# Pendu_LED_10mm.net
KiCad netlist of a schematic drawn in EasyEDA
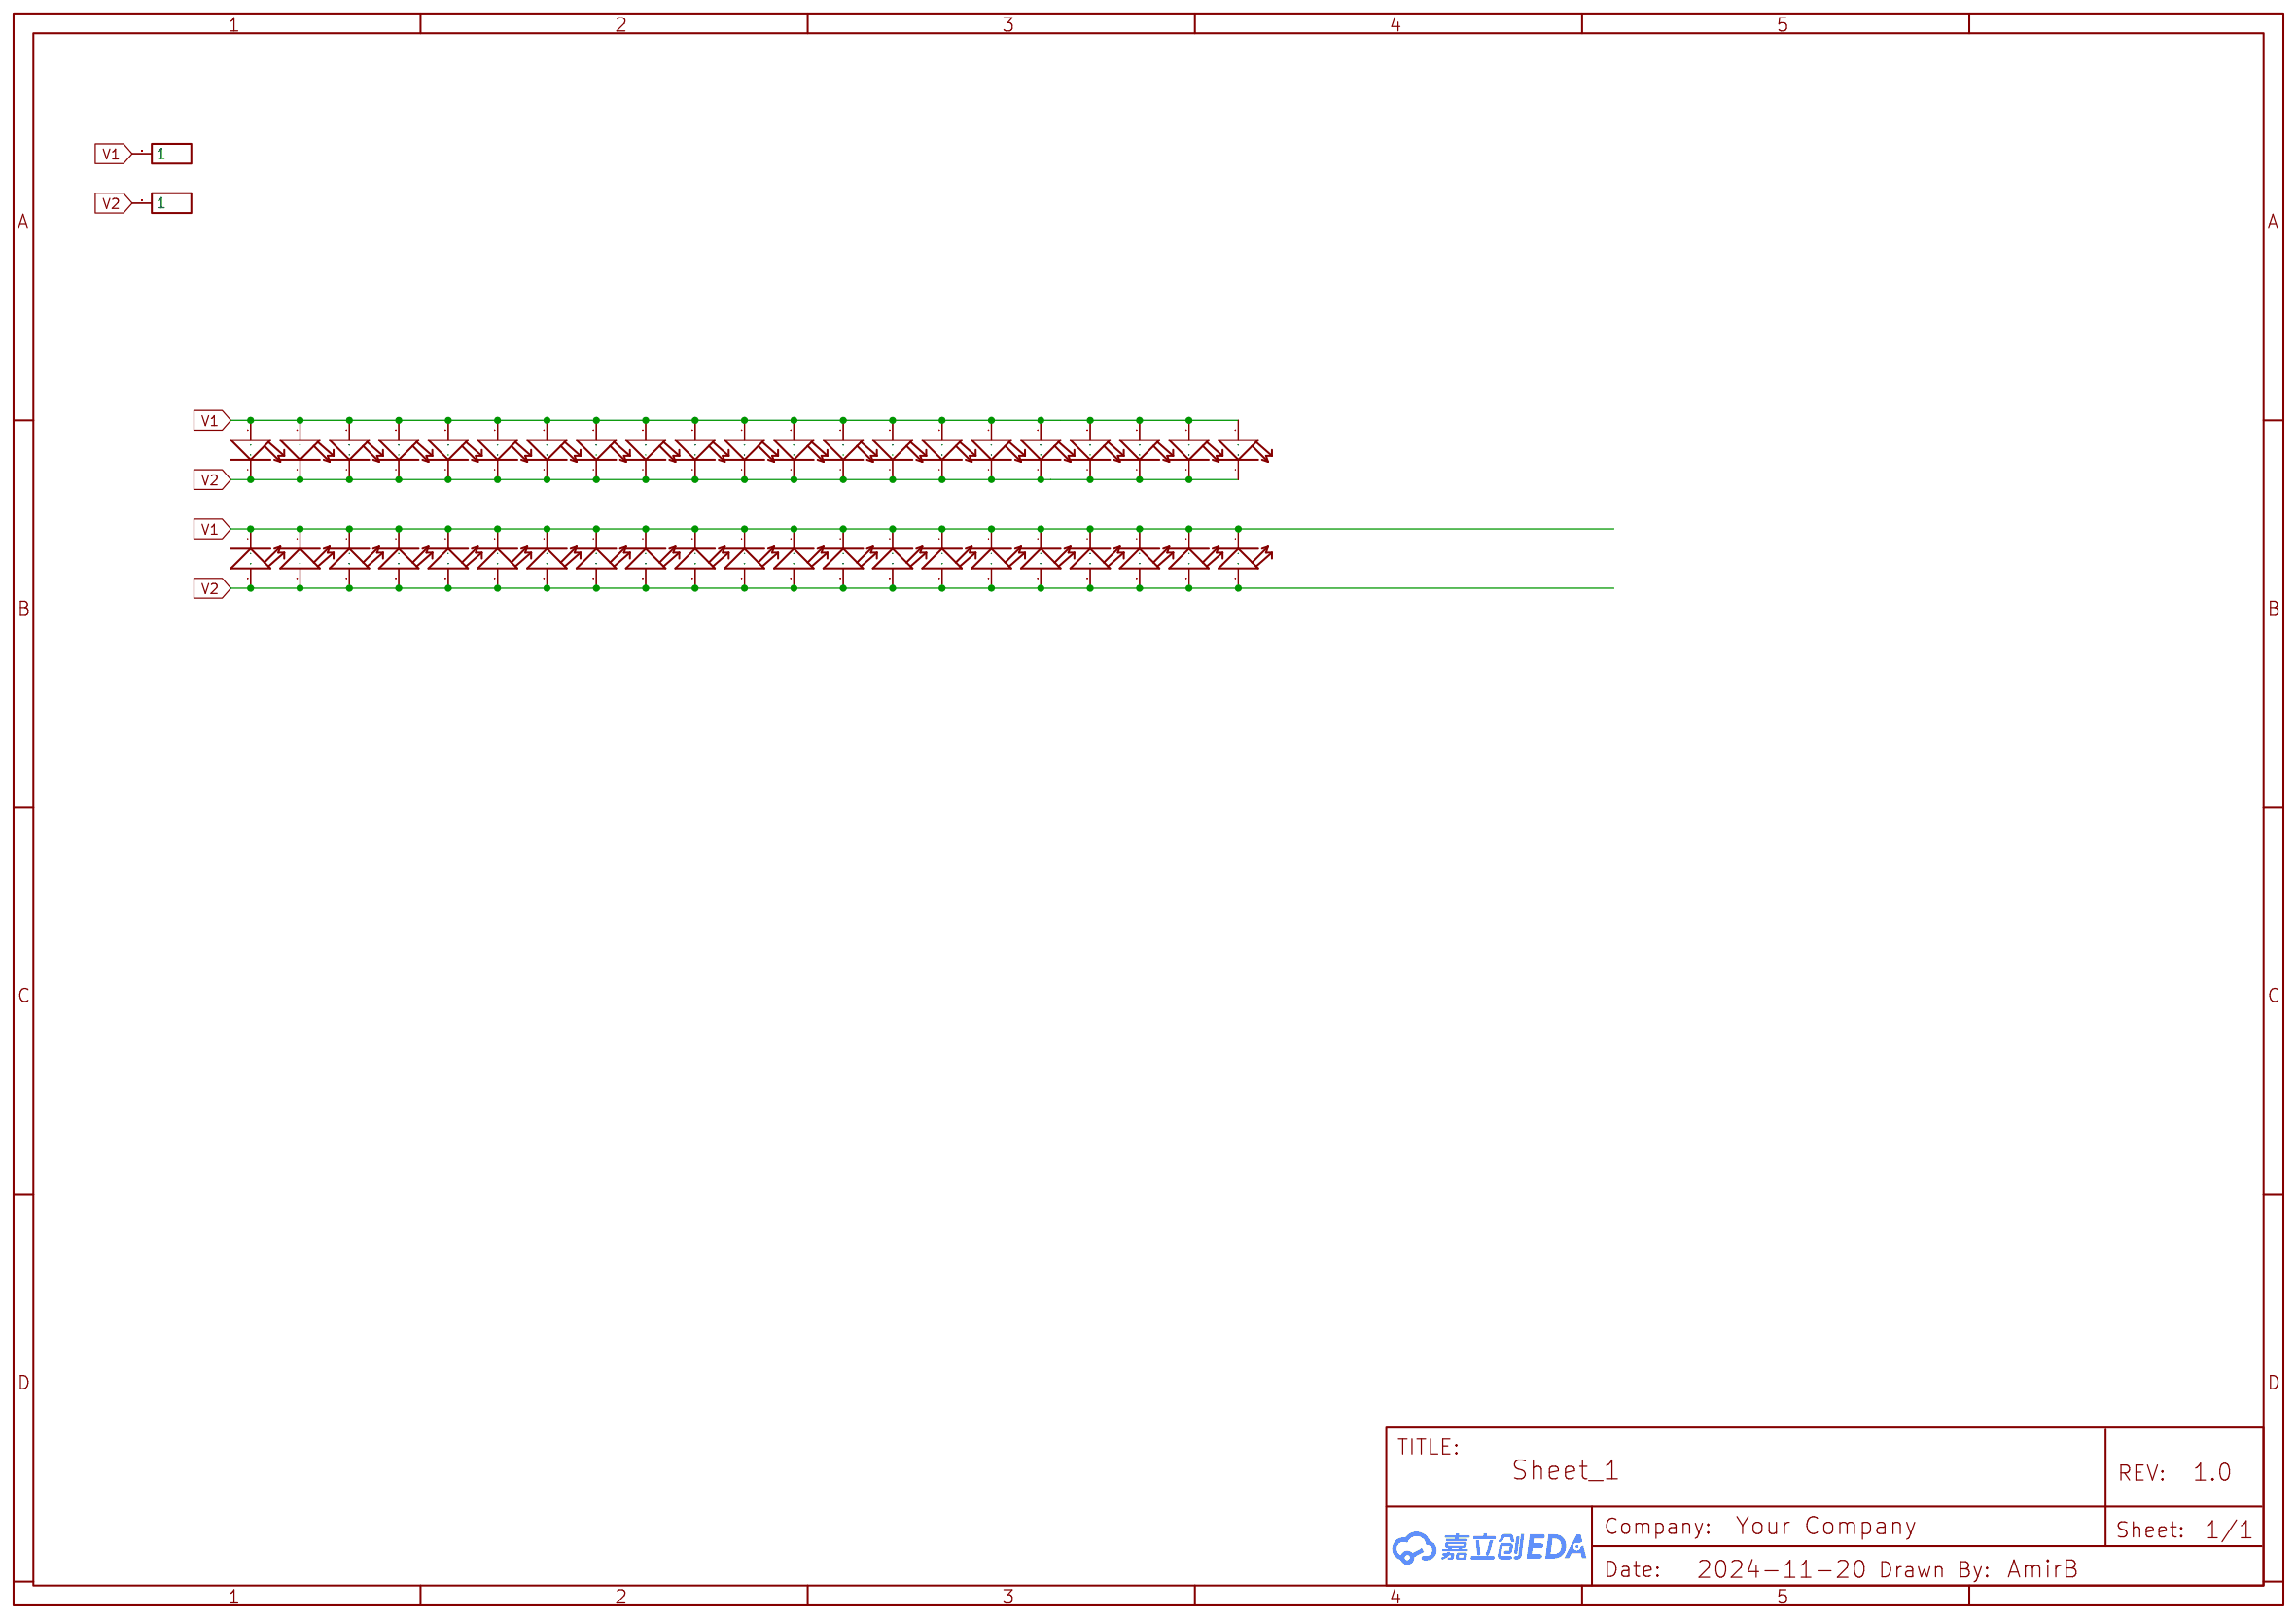
[diagram p0: schematic sheet]

(export (version "E")
  (design (tool "Eeschema 10.0.6"))
  (components
    (comp (ref "J1")
      (value "HDR-M-2.54_1x1")
      (fields (field (name "BOM_Supplier Part") "C81276"))
      (libsource (lib "") (part "HDR-M-2.54_1x1"))
    )
    (comp (ref "J2")
      (value "HDR-M-2.54_1x1")
      (fields (field (name "BOM_Supplier Part") "C81276"))
      (libsource (lib "") (part "HDR-M-2.54_1x1"))
    )
    (comp (ref "LD1") (value "1004OUW") (libsource (lib "") (part "1004OUW_1")))
    (comp (ref "LD2") (value "1004OUW") (libsource (lib "") (part "1004OUW_1")))
    (comp (ref "LD3") (value "1004OUW") (libsource (lib "") (part "1004OUW_1")))
    (comp (ref "LD4") (value "1004OUW") (libsource (lib "") (part "1004OUW_1")))
    (comp (ref "LD5") (value "1004OUW") (libsource (lib "") (part "1004OUW_1")))
    (comp (ref "LD6") (value "1004OUW") (libsource (lib "") (part "1004OUW_1")))
    (comp (ref "LD7") (value "1004OUW") (libsource (lib "") (part "1004OUW_1")))
    (comp (ref "LD8") (value "1004OUW") (libsource (lib "") (part "1004OUW_1")))
    (comp (ref "LD9") (value "1004OUW") (libsource (lib "") (part "1004OUW_1")))
    (comp (ref "LD10") (value "1004OUW") (libsource (lib "") (part "1004OUW_1")))
    (comp (ref "LD11") (value "1004OUW") (libsource (lib "") (part "1004OUW_1")))
    (comp (ref "LD12") (value "1004OUW") (libsource (lib "") (part "1004OUW_1")))
    (comp (ref "LD13") (value "1004OUW") (libsource (lib "") (part "1004OUW_1")))
    (comp (ref "LD14") (value "1004OUW") (libsource (lib "") (part "1004OUW_1")))
    (comp (ref "LD15") (value "1004OUW") (libsource (lib "") (part "1004OUW_1")))
    (comp (ref "LD16") (value "1004OUW") (libsource (lib "") (part "1004OUW_1")))
    (comp (ref "LD17") (value "1004OUW") (libsource (lib "") (part "1004OUW_1")))
    (comp (ref "LD18") (value "1004OUW") (libsource (lib "") (part "1004OUW_1")))
    (comp (ref "LD19") (value "1004OUW") (libsource (lib "") (part "1004OUW_1")))
    (comp (ref "LD20") (value "1004OUW") (libsource (lib "") (part "1004OUW_1")))
    (comp (ref "LD21") (value "1004OUW") (libsource (lib "") (part "1004OUW_1")))
    (comp (ref "LU1") (value "1004OUW") (libsource (lib "") (part "1004OUW")))
    (comp (ref "LU2") (value "1004OUW") (libsource (lib "") (part "1004OUW")))
    (comp (ref "LU3") (value "1004OUW") (libsource (lib "") (part "1004OUW")))
    (comp (ref "LU4") (value "1004OUW") (libsource (lib "") (part "1004OUW")))
    (comp (ref "LU5") (value "1004OUW") (libsource (lib "") (part "1004OUW")))
    (comp (ref "LU6") (value "1004OUW") (libsource (lib "") (part "1004OUW")))
    (comp (ref "LU7") (value "1004OUW") (libsource (lib "") (part "1004OUW")))
    (comp (ref "LU8") (value "1004OUW") (libsource (lib "") (part "1004OUW")))
    (comp (ref "LU9") (value "1004OUW") (libsource (lib "") (part "1004OUW")))
    (comp (ref "LU10") (value "1004OUW") (libsource (lib "") (part "1004OUW")))
    (comp (ref "LU11") (value "1004OUW") (libsource (lib "") (part "1004OUW")))
    (comp (ref "LU12") (value "1004OUW") (libsource (lib "") (part "1004OUW")))
    (comp (ref "LU13") (value "1004OUW") (libsource (lib "") (part "1004OUW")))
    (comp (ref "LU14") (value "1004OUW") (libsource (lib "") (part "1004OUW")))
    (comp (ref "LU15") (value "1004OUW") (libsource (lib "") (part "1004OUW")))
    (comp (ref "LU16") (value "1004OUW") (libsource (lib "") (part "1004OUW")))
    (comp (ref "LU17") (value "1004OUW") (libsource (lib "") (part "1004OUW")))
    (comp (ref "LU18") (value "1004OUW") (libsource (lib "") (part "1004OUW")))
    (comp (ref "LU19") (value "1004OUW") (libsource (lib "") (part "1004OUW")))
    (comp (ref "LU20") (value "1004OUW") (libsource (lib "") (part "1004OUW")))
    (comp (ref "LU21") (value "1004OUW") (libsource (lib "") (part "1004OUW")))
  )
  (nets
    (net (code "1") (name "V1") (class "Default")
      (node (ref "J1") (pin "1") (pinfunction "1_1") (pintype "input"))
      (node (ref "LD1") (pin "-") (pinfunction "-_-") (pintype "unspecified"))
      (node (ref "LD10") (pin "-") (pinfunction "-_-") (pintype "unspecified"))
      (node (ref "LD11") (pin "-") (pinfunction "-_-") (pintype "unspecified"))
      (node (ref "LD12") (pin "-") (pinfunction "-_-") (pintype "unspecified"))
      (node (ref "LD13") (pin "-") (pinfunction "-_-") (pintype "unspecified"))
      (node (ref "LD14") (pin "-") (pinfunction "-_-") (pintype "unspecified"))
      (node (ref "LD15") (pin "-") (pinfunction "-_-") (pintype "unspecified"))
      (node (ref "LD16") (pin "-") (pinfunction "-_-") (pintype "unspecified"))
      (node (ref "LD17") (pin "-") (pinfunction "-_-") (pintype "unspecified"))
      (node (ref "LD18") (pin "-") (pinfunction "-_-") (pintype "unspecified"))
      (node (ref "LD19") (pin "-") (pinfunction "-_-") (pintype "unspecified"))
      (node (ref "LD2") (pin "-") (pinfunction "-_-") (pintype "unspecified"))
      (node (ref "LD20") (pin "-") (pinfunction "-_-") (pintype "unspecified"))
      (node (ref "LD21") (pin "-") (pinfunction "-_-") (pintype "unspecified"))
      (node (ref "LD3") (pin "-") (pinfunction "-_-") (pintype "unspecified"))
      (node (ref "LD4") (pin "-") (pinfunction "-_-") (pintype "unspecified"))
      (node (ref "LD5") (pin "-") (pinfunction "-_-") (pintype "unspecified"))
      (node (ref "LD6") (pin "-") (pinfunction "-_-") (pintype "unspecified"))
      (node (ref "LD7") (pin "-") (pinfunction "-_-") (pintype "unspecified"))
      (node (ref "LD8") (pin "-") (pinfunction "-_-") (pintype "unspecified"))
      (node (ref "LD9") (pin "-") (pinfunction "-_-") (pintype "unspecified"))
      (node (ref "LU1") (pin "+") (pinfunction "+_+") (pintype "unspecified"))
      (node (ref "LU10") (pin "+") (pinfunction "+_+") (pintype "unspecified"))
      (node (ref "LU11") (pin "+") (pinfunction "+_+") (pintype "unspecified"))
      (node (ref "LU12") (pin "+") (pinfunction "+_+") (pintype "unspecified"))
      (node (ref "LU13") (pin "+") (pinfunction "+_+") (pintype "unspecified"))
      (node (ref "LU14") (pin "+") (pinfunction "+_+") (pintype "unspecified"))
      (node (ref "LU15") (pin "+") (pinfunction "+_+") (pintype "unspecified"))
      (node (ref "LU16") (pin "+") (pinfunction "+_+") (pintype "unspecified"))
      (node (ref "LU17") (pin "+") (pinfunction "+_+") (pintype "unspecified"))
      (node (ref "LU18") (pin "+") (pinfunction "+_+") (pintype "unspecified"))
      (node (ref "LU19") (pin "+") (pinfunction "+_+") (pintype "unspecified"))
      (node (ref "LU2") (pin "+") (pinfunction "+_+") (pintype "unspecified"))
      (node (ref "LU20") (pin "+") (pinfunction "+_+") (pintype "unspecified"))
      (node (ref "LU21") (pin "+") (pinfunction "+_+") (pintype "unspecified"))
      (node (ref "LU3") (pin "+") (pinfunction "+_+") (pintype "unspecified"))
      (node (ref "LU4") (pin "+") (pinfunction "+_+") (pintype "unspecified"))
      (node (ref "LU5") (pin "+") (pinfunction "+_+") (pintype "unspecified"))
      (node (ref "LU6") (pin "+") (pinfunction "+_+") (pintype "unspecified"))
      (node (ref "LU7") (pin "+") (pinfunction "+_+") (pintype "unspecified"))
      (node (ref "LU8") (pin "+") (pinfunction "+_+") (pintype "unspecified"))
      (node (ref "LU9") (pin "+") (pinfunction "+_+") (pintype "unspecified"))
    )
    (net (code "2") (name "V2") (class "Default")
      (node (ref "J2") (pin "1") (pinfunction "1_1") (pintype "input"))
      (node (ref "LD1") (pin "+") (pinfunction "+_+") (pintype "unspecified"))
      (node (ref "LD10") (pin "+") (pinfunction "+_+") (pintype "unspecified"))
      (node (ref "LD11") (pin "+") (pinfunction "+_+") (pintype "unspecified"))
      (node (ref "LD12") (pin "+") (pinfunction "+_+") (pintype "unspecified"))
      (node (ref "LD13") (pin "+") (pinfunction "+_+") (pintype "unspecified"))
      (node (ref "LD14") (pin "+") (pinfunction "+_+") (pintype "unspecified"))
      (node (ref "LD15") (pin "+") (pinfunction "+_+") (pintype "unspecified"))
      (node (ref "LD16") (pin "+") (pinfunction "+_+") (pintype "unspecified"))
      (node (ref "LD17") (pin "+") (pinfunction "+_+") (pintype "unspecified"))
      (node (ref "LD18") (pin "+") (pinfunction "+_+") (pintype "unspecified"))
      (node (ref "LD19") (pin "+") (pinfunction "+_+") (pintype "unspecified"))
      (node (ref "LD2") (pin "+") (pinfunction "+_+") (pintype "unspecified"))
      (node (ref "LD20") (pin "+") (pinfunction "+_+") (pintype "unspecified"))
      (node (ref "LD21") (pin "+") (pinfunction "+_+") (pintype "unspecified"))
      (node (ref "LD3") (pin "+") (pinfunction "+_+") (pintype "unspecified"))
      (node (ref "LD4") (pin "+") (pinfunction "+_+") (pintype "unspecified"))
      (node (ref "LD5") (pin "+") (pinfunction "+_+") (pintype "unspecified"))
      (node (ref "LD6") (pin "+") (pinfunction "+_+") (pintype "unspecified"))
      (node (ref "LD7") (pin "+") (pinfunction "+_+") (pintype "unspecified"))
      (node (ref "LD8") (pin "+") (pinfunction "+_+") (pintype "unspecified"))
      (node (ref "LD9") (pin "+") (pinfunction "+_+") (pintype "unspecified"))
      (node (ref "LU1") (pin "-") (pinfunction "-_-") (pintype "unspecified"))
      (node (ref "LU10") (pin "-") (pinfunction "-_-") (pintype "unspecified"))
      (node (ref "LU11") (pin "-") (pinfunction "-_-") (pintype "unspecified"))
      (node (ref "LU12") (pin "-") (pinfunction "-_-") (pintype "unspecified"))
      (node (ref "LU13") (pin "-") (pinfunction "-_-") (pintype "unspecified"))
      (node (ref "LU14") (pin "-") (pinfunction "-_-") (pintype "unspecified"))
      (node (ref "LU15") (pin "-") (pinfunction "-_-") (pintype "unspecified"))
      (node (ref "LU16") (pin "-") (pinfunction "-_-") (pintype "unspecified"))
      (node (ref "LU17") (pin "-") (pinfunction "-_-") (pintype "unspecified"))
      (node (ref "LU18") (pin "-") (pinfunction "-_-") (pintype "unspecified"))
      (node (ref "LU19") (pin "-") (pinfunction "-_-") (pintype "unspecified"))
      (node (ref "LU2") (pin "-") (pinfunction "-_-") (pintype "unspecified"))
      (node (ref "LU20") (pin "-") (pinfunction "-_-") (pintype "unspecified"))
      (node (ref "LU21") (pin "-") (pinfunction "-_-") (pintype "unspecified"))
      (node (ref "LU3") (pin "-") (pinfunction "-_-") (pintype "unspecified"))
      (node (ref "LU4") (pin "-") (pinfunction "-_-") (pintype "unspecified"))
      (node (ref "LU5") (pin "-") (pinfunction "-_-") (pintype "unspecified"))
      (node (ref "LU6") (pin "-") (pinfunction "-_-") (pintype "unspecified"))
      (node (ref "LU7") (pin "-") (pinfunction "-_-") (pintype "unspecified"))
      (node (ref "LU8") (pin "-") (pinfunction "-_-") (pintype "unspecified"))
      (node (ref "LU9") (pin "-") (pinfunction "-_-") (pintype "unspecified"))
    )
  )
)
